# LED_STRING_MANAGER_REV_1.net
KiCad netlist of a schematic drawn in EAGLE
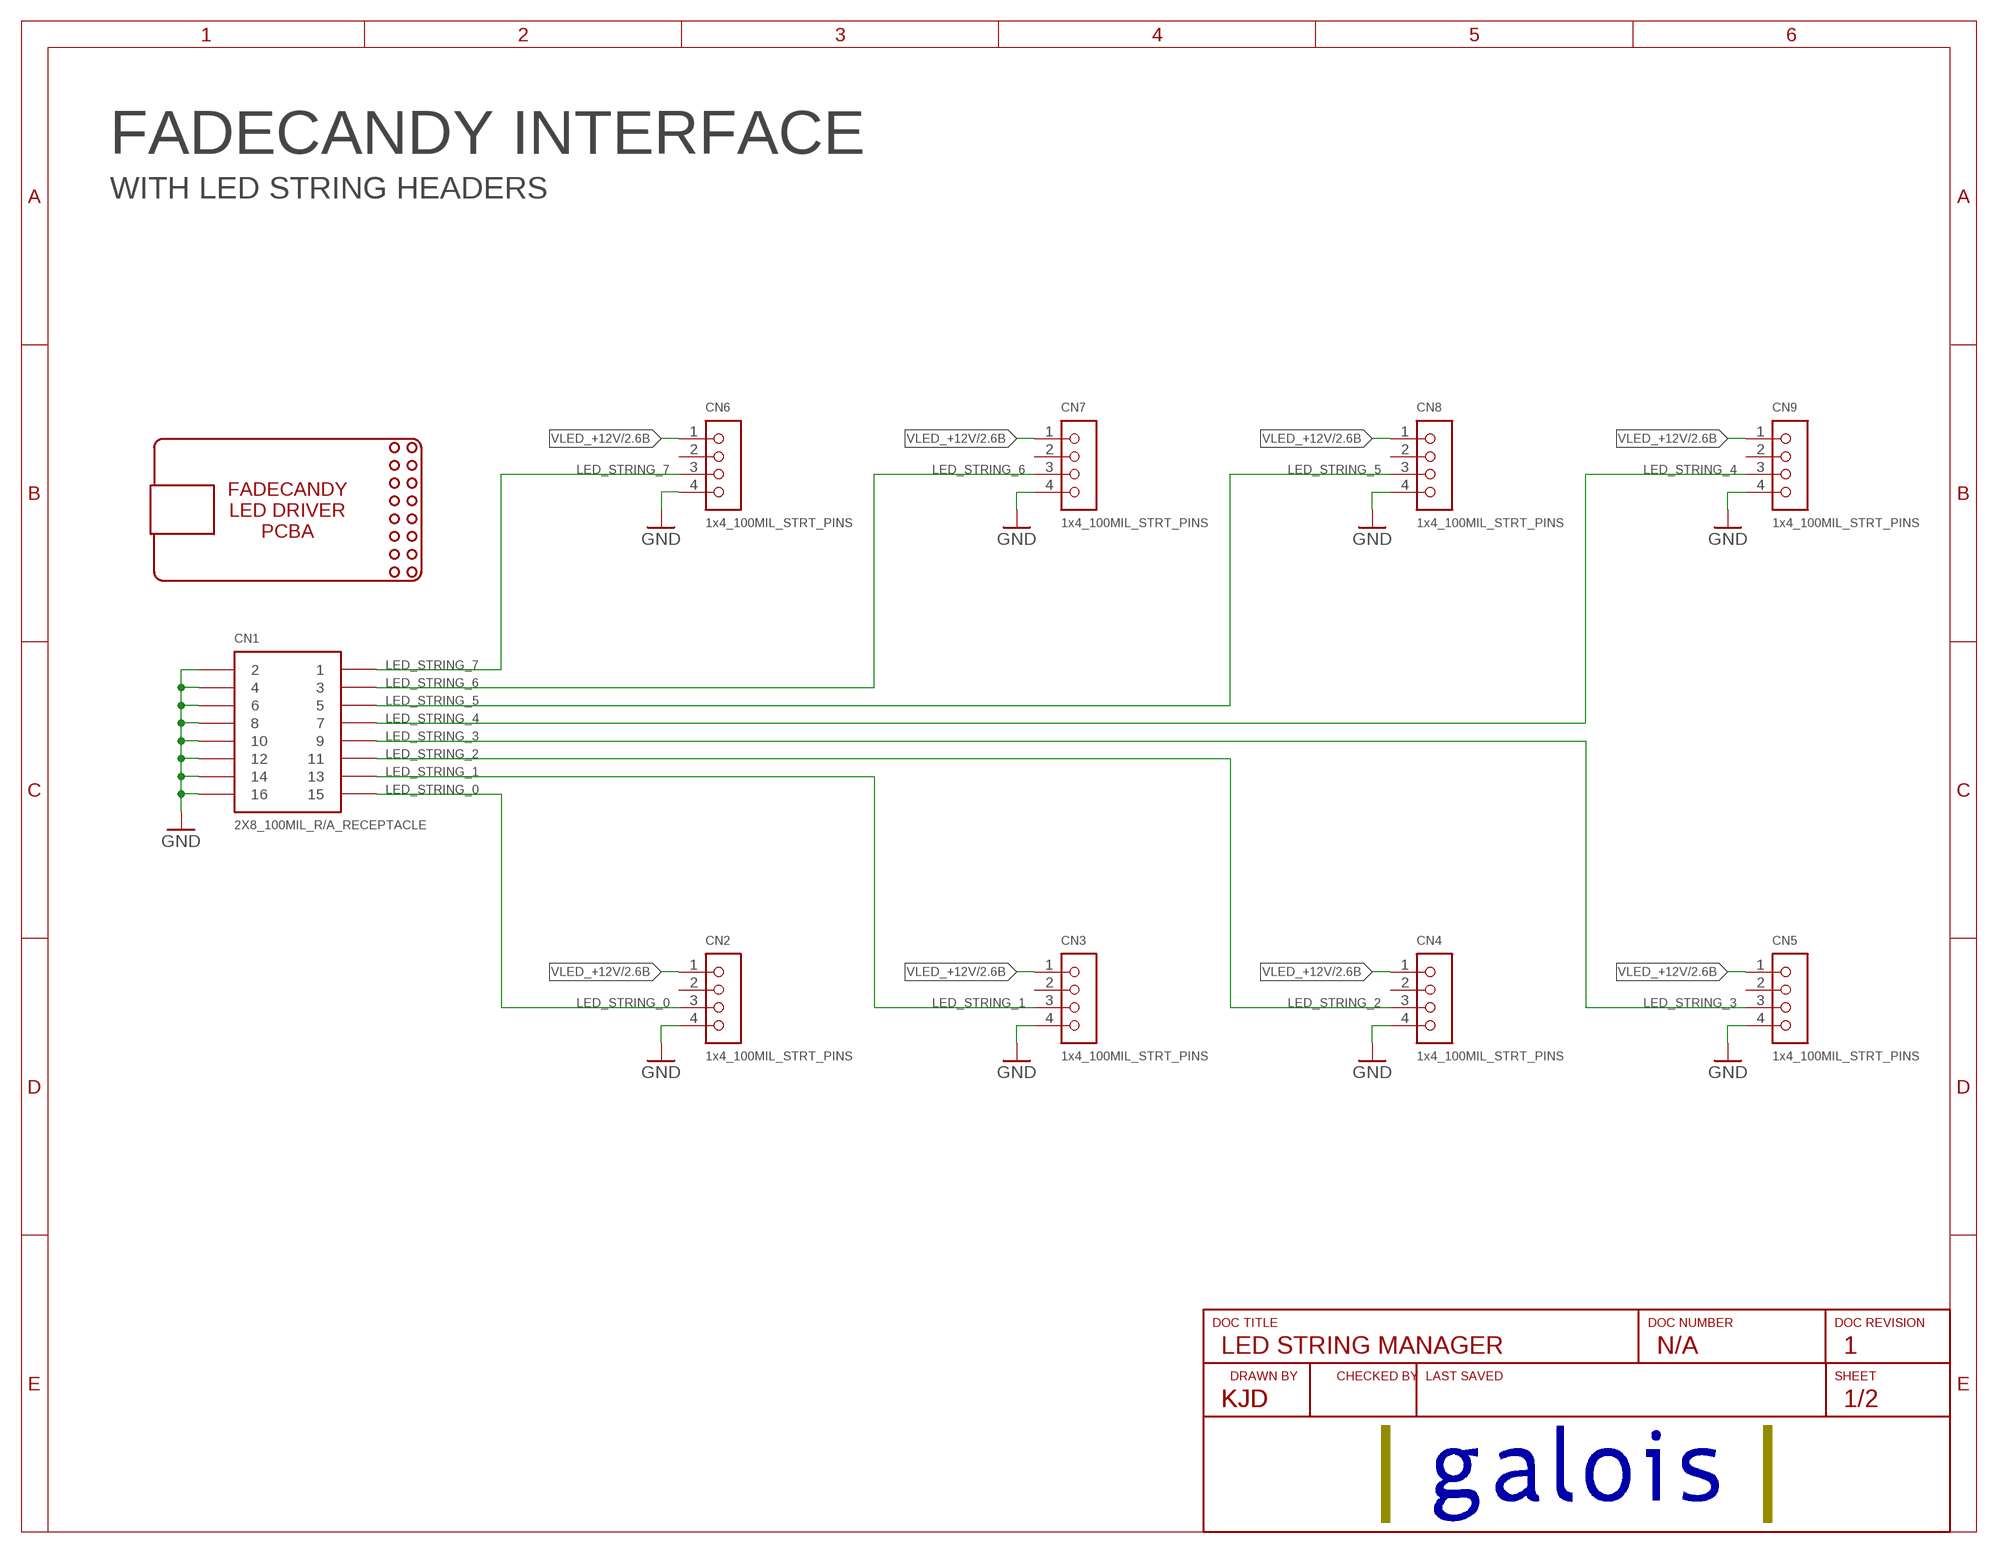
[diagram p0: schematic, sheet 1]
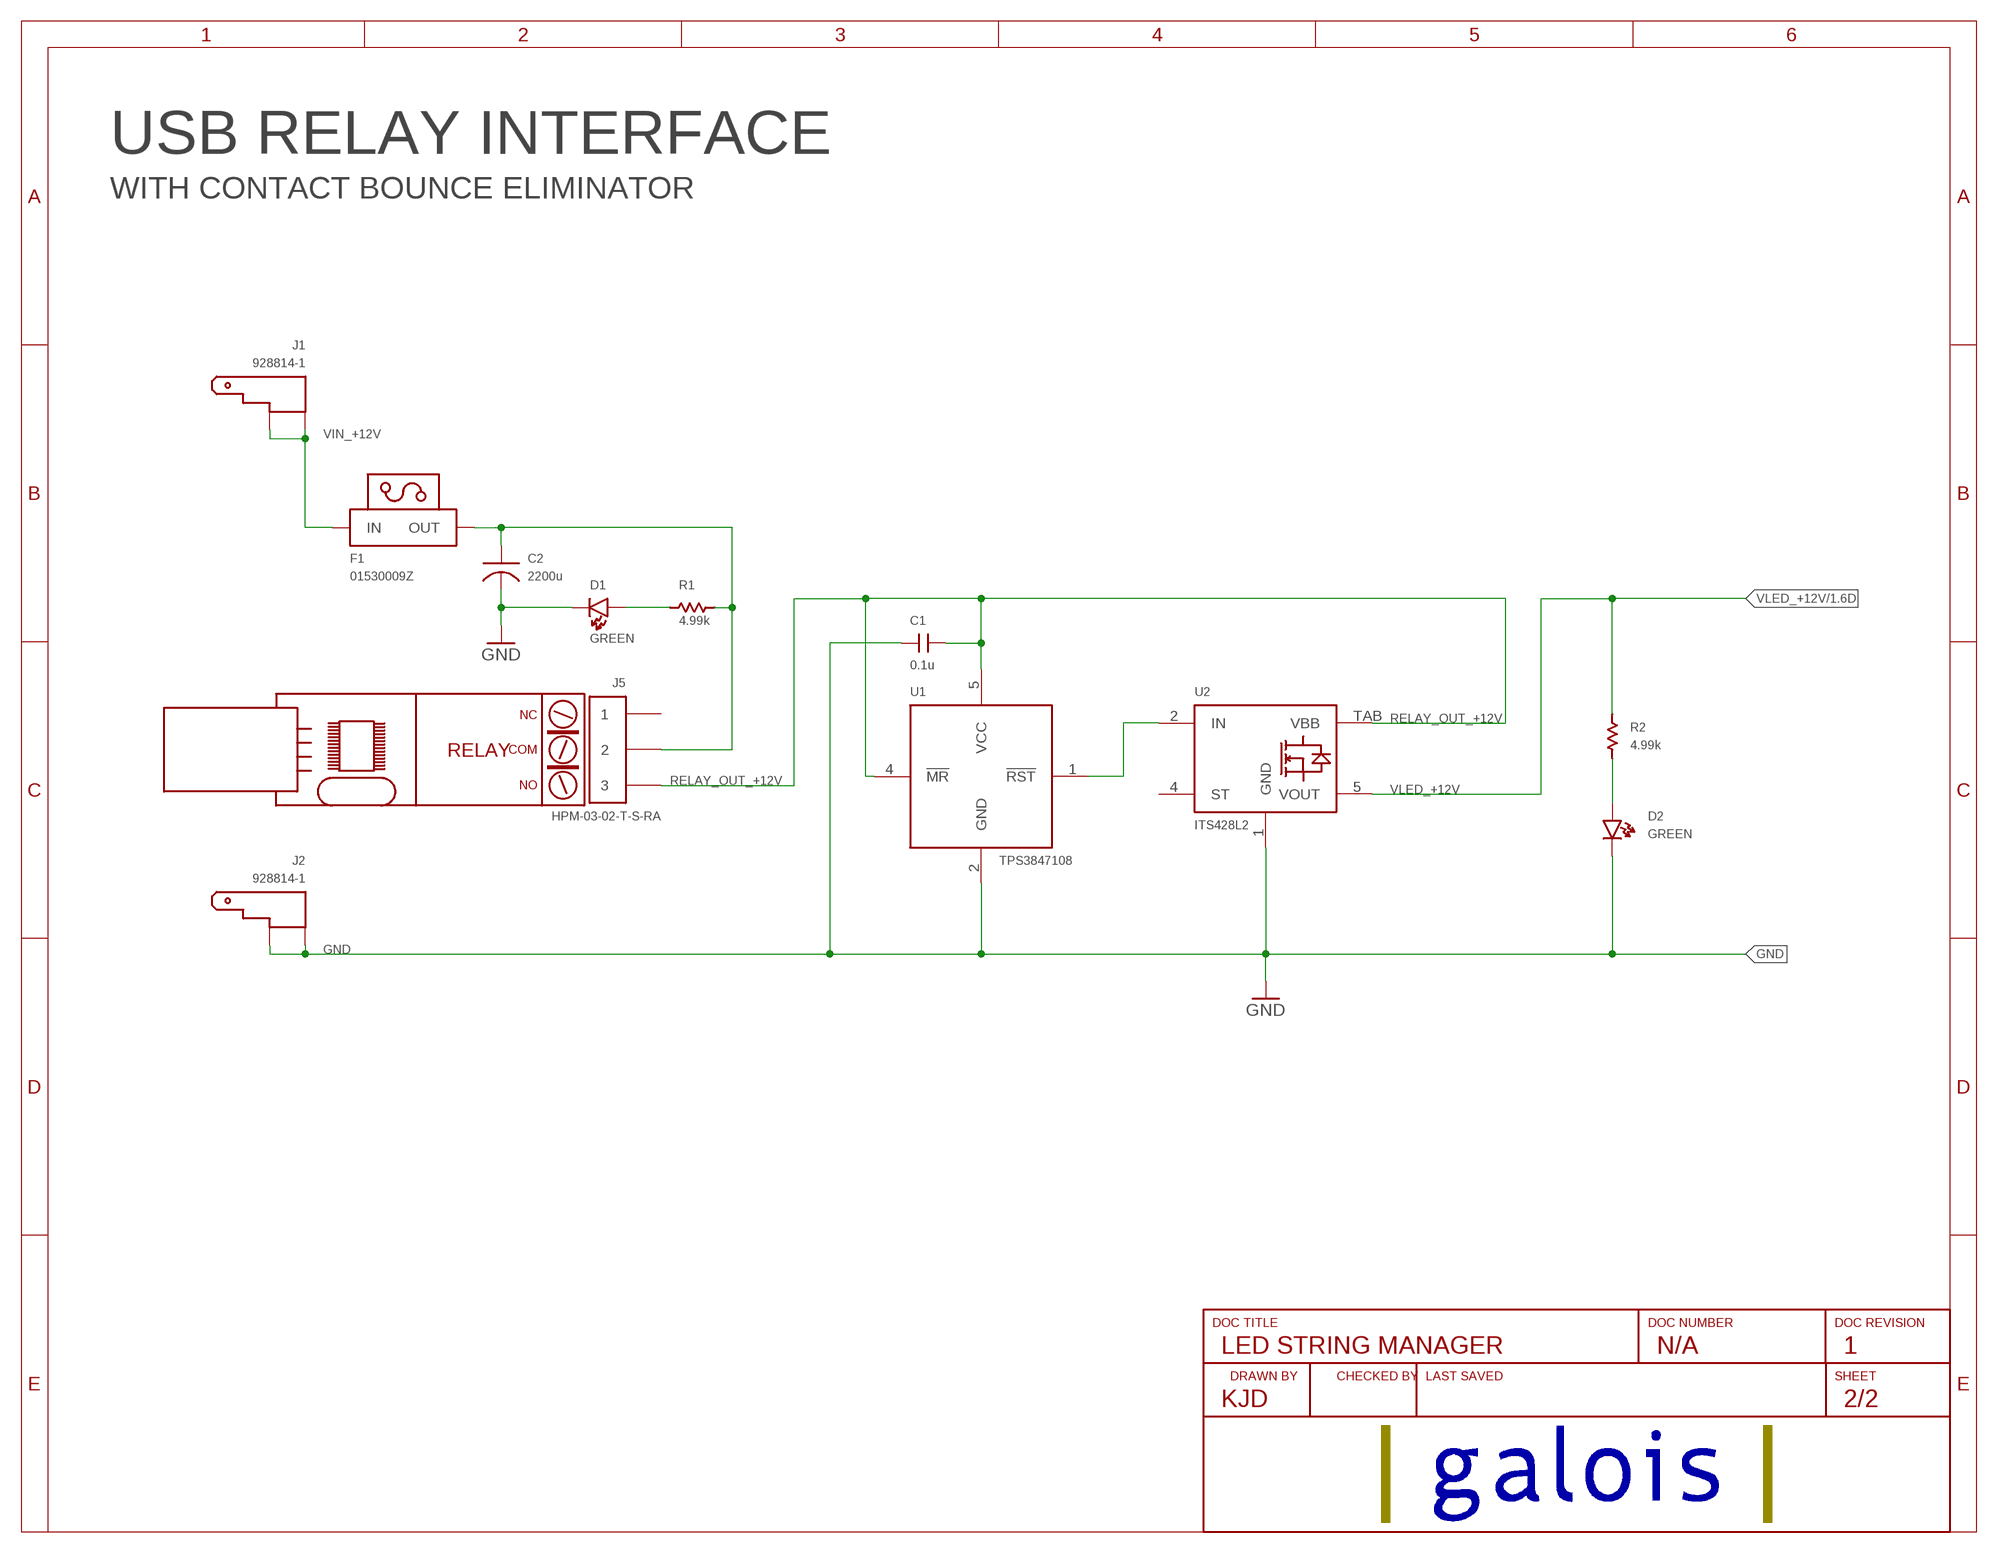
[diagram p1: schematic, sheet 2]

(export (version "E")
  (design (tool "Eeschema 10.0.6"))
  (components
    (comp (ref "CN1")
      (value "2X8_100MIL_R/A_RECEPTACLE")
      (footprint "eagle-import:2X8_100MIL_R_A")
      (fields (field (name "MPN") "PPPC082LJBN-RC"))
      (libsource (lib "eagle-import") (part "2X8_RIGHT_ANGLE"))
    )
    (comp (ref "CN2")
      (value "1x4_100MIL_STRT_PINS")
      (footprint "eagle-import:1X4_0901361204")
      (fields (field (name "MPN") "0901361204"))
      (libsource (lib "eagle-import") (part "MOLEX_CGRID_III_0901361204"))
    )
    (comp (ref "CN3")
      (value "1x4_100MIL_STRT_PINS")
      (footprint "eagle-import:1X4_0901361204")
      (fields (field (name "MPN") "0901361204"))
      (libsource (lib "eagle-import") (part "MOLEX_CGRID_III_0901361204"))
    )
    (comp (ref "CN4")
      (value "1x4_100MIL_STRT_PINS")
      (footprint "eagle-import:1X4_0901361204")
      (fields (field (name "MPN") "0901361204"))
      (libsource (lib "eagle-import") (part "MOLEX_CGRID_III_0901361204"))
    )
    (comp (ref "CN5")
      (value "1x4_100MIL_STRT_PINS")
      (footprint "eagle-import:1X4_0901361204")
      (fields (field (name "MPN") "0901361204"))
      (libsource (lib "eagle-import") (part "MOLEX_CGRID_III_0901361204"))
    )
    (comp (ref "CN6")
      (value "1x4_100MIL_STRT_PINS")
      (footprint "eagle-import:1X4_0901361204")
      (fields (field (name "MPN") "0901361204"))
      (libsource (lib "eagle-import") (part "MOLEX_CGRID_III_0901361204"))
    )
    (comp (ref "CN7")
      (value "1x4_100MIL_STRT_PINS")
      (footprint "eagle-import:1X4_0901361204")
      (fields (field (name "MPN") "0901361204"))
      (libsource (lib "eagle-import") (part "MOLEX_CGRID_III_0901361204"))
    )
    (comp (ref "CN8")
      (value "1x4_100MIL_STRT_PINS")
      (footprint "eagle-import:1X4_0901361204")
      (fields (field (name "MPN") "0901361204"))
      (libsource (lib "eagle-import") (part "MOLEX_CGRID_III_0901361204"))
    )
    (comp (ref "CN9")
      (value "1x4_100MIL_STRT_PINS")
      (footprint "eagle-import:1X4_0901361204")
      (fields (field (name "MPN") "0901361204"))
      (libsource (lib "eagle-import") (part "MOLEX_CGRID_III_0901361204"))
    )
    (comp (ref "U$3")
      (value "FADECANDY_PCB_FOOTPRINT")
      (footprint "eagle-import:FADECANDY_PCB_FOOTPRINT")
      (libsource (lib "eagle-import") (part "FADECANDY_PCB_FOOTPRINT"))
    )
    (comp (ref "C1")
      (value "0.1u")
      (footprint "eagle-import:EIA0603")
      (fields (field (name "MPN") "CL10B104KB8NNNC"))
      (libsource (lib "eagle-import") (part "C_SMDC0603"))
    )
    (comp (ref "C2")
      (value "2200u")
      (footprint "eagle-import:PANASONIC_HD_12.5MM")
      (fields (field (name "MPN") "EEU-HD1E222"))
      (libsource (lib "eagle-import") (part "C_POLARIZED_DIA_12.5MM_LEADS_5MM"))
    )
    (comp (ref "D1")
      (value "GREEN")
      (footprint "eagle-import:EIA0603_LED")
      (fields (field (name "MPN") "LG Q396-PS-35"))
      (libsource (lib "eagle-import") (part "LED_SMD"))
    )
    (comp (ref "D2")
      (value "GREEN")
      (footprint "eagle-import:EIA0603_LED")
      (fields (field (name "MPN") "LG Q396-PS-35"))
      (libsource (lib "eagle-import") (part "LED_SMD"))
    )
    (comp (ref "F1")
      (value "01530009Z")
      (footprint "eagle-import:LITTELFUSE_MINI_BLADE_HOLDER_01530009")
      (fields (field (name "MPN") "01530009Z"))
      (libsource (lib "eagle-import") (part "FUSE_HOLDER_AUTOMOTIVE_MINI_BLADE"))
    )
    (comp (ref "J1")
      (value "928814-1")
      (footprint "eagle-import:FASTON_MALE_SERIES_250_THRU_R_A")
      (fields (field (name "MPN") "928814-1"))
      (libsource (lib "eagle-import") (part "FASTON_PCB_THRU_R/A"))
    )
    (comp (ref "J2")
      (value "928814-1")
      (footprint "eagle-import:FASTON_MALE_SERIES_250_THRU_R_A")
      (fields (field (name "MPN") "928814-1"))
      (libsource (lib "eagle-import") (part "FASTON_PCB_THRU_R/A"))
    )
    (comp (ref "J5")
      (value "HPM-03-02-T-S-RA")
      (footprint "eagle-import:HPM_1X3_R_A")
      (fields (field (name "MPN") "HPM-03-02-T-S-RA"))
      (libsource (lib "eagle-import") (part "HPM_1X3_R/A"))
    )
    (comp (ref "R1")
      (value "4.99k")
      (footprint "eagle-import:EIA0603")
      (fields (field (name "MPN") "ERJ-3EKF4991V"))
      (libsource (lib "eagle-import") (part "R_SMDR0603"))
    )
    (comp (ref "R2")
      (value "4.99k")
      (footprint "eagle-import:EIA0603")
      (fields (field (name "MPN") "ERJ-3EKF4991V"))
      (libsource (lib "eagle-import") (part "R_SMDR0603"))
    )
    (comp (ref "U$4")
      (value "USB_RELAY_PCB_FOOTPRINT")
      (footprint "eagle-import:USB_RELAY_PCB_FOOTPRINT")
      (libsource (lib "eagle-import") (part "USB_RELAY_PCB_FOOTPRINT"))
    )
    (comp (ref "U1")
      (value "TPS3847108")
      (footprint "eagle-import:SOT23-5")
      (fields (field (name "MPN") "TPS3847108DBVR"))
      (libsource (lib "eagle-import") (part "TPS3847"))
    )
    (comp (ref "U2")
      (value "ITS428L2")
      (footprint "eagle-import:PG-TO252-5-11")
      (fields (field (name "MPN") "ITS428L2ATMA1"))
      (libsource (lib "eagle-import") (part "ITS428L2"))
    )
  )
  (nets
    (net (code "1") (name "GND") (class "Default")
      (node (ref "C1") (pin "P$1") (pinfunction "P$1_P$1") (pintype "passive"))
      (node (ref "C2") (pin "C-") (pinfunction "C-_C-") (pintype "bidirectional"))
      (node (ref "CN1") (pin "10") (pinfunction "10_10") (pintype "bidirectional"))
      (node (ref "CN1") (pin "12") (pinfunction "12_12") (pintype "bidirectional"))
      (node (ref "CN1") (pin "14") (pinfunction "14_14") (pintype "bidirectional"))
      (node (ref "CN1") (pin "16") (pinfunction "16_16") (pintype "bidirectional"))
      (node (ref "CN1") (pin "2") (pinfunction "2_2") (pintype "bidirectional"))
      (node (ref "CN1") (pin "4") (pinfunction "4_4") (pintype "bidirectional"))
      (node (ref "CN1") (pin "6") (pinfunction "6_6") (pintype "bidirectional"))
      (node (ref "CN1") (pin "8") (pinfunction "8_8") (pintype "bidirectional"))
      (node (ref "CN2") (pin "4") (pinfunction "4_4") (pintype "bidirectional"))
      (node (ref "CN3") (pin "4") (pinfunction "4_4") (pintype "bidirectional"))
      (node (ref "CN4") (pin "4") (pinfunction "4_4") (pintype "bidirectional"))
      (node (ref "CN5") (pin "4") (pinfunction "4_4") (pintype "bidirectional"))
      (node (ref "CN6") (pin "4") (pinfunction "4_4") (pintype "bidirectional"))
      (node (ref "CN7") (pin "4") (pinfunction "4_4") (pintype "bidirectional"))
      (node (ref "CN8") (pin "4") (pinfunction "4_4") (pintype "bidirectional"))
      (node (ref "CN9") (pin "4") (pinfunction "4_4") (pintype "bidirectional"))
      (node (ref "D1") (pin "C") (pinfunction "C_C") (pintype "passive"))
      (node (ref "D2") (pin "C") (pinfunction "C_C") (pintype "passive"))
      (node (ref "J2") (pin "1") (pinfunction "1_1") (pintype "bidirectional"))
      (node (ref "J2") (pin "2") (pinfunction "2_2") (pintype "bidirectional"))
      (node (ref "U1") (pin "2") (pinfunction "GND_2") (pintype "bidirectional"))
      (node (ref "U2") (pin "1") (pinfunction "GND_1") (pintype "bidirectional"))
    )
    (net (code "2") (name "LED_STRING_0") (class "Default")
      (node (ref "CN1") (pin "15") (pinfunction "15_15") (pintype "bidirectional"))
      (node (ref "CN2") (pin "3") (pinfunction "3_3") (pintype "bidirectional"))
    )
    (net (code "3") (name "LED_STRING_1") (class "Default")
      (node (ref "CN1") (pin "13") (pinfunction "13_13") (pintype "bidirectional"))
      (node (ref "CN3") (pin "3") (pinfunction "3_3") (pintype "bidirectional"))
    )
    (net (code "4") (name "LED_STRING_2") (class "Default")
      (node (ref "CN1") (pin "11") (pinfunction "11_11") (pintype "bidirectional"))
      (node (ref "CN4") (pin "3") (pinfunction "3_3") (pintype "bidirectional"))
    )
    (net (code "5") (name "LED_STRING_3") (class "Default")
      (node (ref "CN1") (pin "9") (pinfunction "9_9") (pintype "bidirectional"))
      (node (ref "CN5") (pin "3") (pinfunction "3_3") (pintype "bidirectional"))
    )
    (net (code "6") (name "LED_STRING_4") (class "Default")
      (node (ref "CN1") (pin "7") (pinfunction "7_7") (pintype "bidirectional"))
      (node (ref "CN9") (pin "3") (pinfunction "3_3") (pintype "bidirectional"))
    )
    (net (code "7") (name "LED_STRING_5") (class "Default")
      (node (ref "CN1") (pin "5") (pinfunction "5_5") (pintype "bidirectional"))
      (node (ref "CN8") (pin "3") (pinfunction "3_3") (pintype "bidirectional"))
    )
    (net (code "8") (name "LED_STRING_6") (class "Default")
      (node (ref "CN1") (pin "3") (pinfunction "3_3") (pintype "bidirectional"))
      (node (ref "CN7") (pin "3") (pinfunction "3_3") (pintype "bidirectional"))
    )
    (net (code "9") (name "LED_STRING_7") (class "Default")
      (node (ref "CN1") (pin "1") (pinfunction "1_1") (pintype "bidirectional"))
      (node (ref "CN6") (pin "3") (pinfunction "3_3") (pintype "bidirectional"))
    )
    (net (code "10") (name "Net-(D1-PadA)") (class "Default")
      (node (ref "D1") (pin "A") (pinfunction "A_A") (pintype "passive"))
      (node (ref "R1") (pin "P$1") (pinfunction "P$1_P$1") (pintype "passive"))
    )
    (net (code "11") (name "Net-(D2-PadA)") (class "Default")
      (node (ref "D2") (pin "A") (pinfunction "A_A") (pintype "passive"))
      (node (ref "R2") (pin "P$1") (pinfunction "P$1_P$1") (pintype "passive"))
    )
    (net (code "12") (name "Net-(F1-OUT)") (class "Default")
      (node (ref "C2") (pin "C+") (pinfunction "C+_C+") (pintype "bidirectional"))
      (node (ref "F1") (pin "2") (pinfunction "OUT_2") (pintype "bidirectional"))
      (node (ref "J5") (pin "2") (pinfunction "2_2") (pintype "bidirectional"))
      (node (ref "R1") (pin "P$2") (pinfunction "P$2_P$2") (pintype "passive"))
    )
    (net (code "13") (name "Net-(U1-~{RST})") (class "Default")
      (node (ref "U1") (pin "1") (pinfunction "~{RST}_1") (pintype "bidirectional"))
      (node (ref "U2") (pin "2") (pinfunction "IN_2") (pintype "bidirectional"))
    )
    (net (code "14") (name "RELAY_OUT_+12V") (class "Default")
      (node (ref "C1") (pin "P$2") (pinfunction "P$2_P$2") (pintype "passive"))
      (node (ref "J5") (pin "3") (pinfunction "3_3") (pintype "bidirectional"))
      (node (ref "U1") (pin "4") (pinfunction "~{MR}_4") (pintype "bidirectional"))
      (node (ref "U1") (pin "5") (pinfunction "VCC_5") (pintype "bidirectional"))
      (node (ref "U2") (pin "TAB") (pinfunction "VBB_TAB") (pintype "bidirectional"))
    )
    (net (code "15") (name "VIN_+12V") (class "Default")
      (node (ref "F1") (pin "1") (pinfunction "IN_1") (pintype "bidirectional"))
      (node (ref "J1") (pin "1") (pinfunction "1_1") (pintype "bidirectional"))
      (node (ref "J1") (pin "2") (pinfunction "2_2") (pintype "bidirectional"))
    )
    (net (code "16") (name "VLED_+12V") (class "Default")
      (node (ref "CN2") (pin "1") (pinfunction "1_1") (pintype "bidirectional"))
      (node (ref "CN3") (pin "1") (pinfunction "1_1") (pintype "bidirectional"))
      (node (ref "CN4") (pin "1") (pinfunction "1_1") (pintype "bidirectional"))
      (node (ref "CN5") (pin "1") (pinfunction "1_1") (pintype "bidirectional"))
      (node (ref "CN6") (pin "1") (pinfunction "1_1") (pintype "bidirectional"))
      (node (ref "CN7") (pin "1") (pinfunction "1_1") (pintype "bidirectional"))
      (node (ref "CN8") (pin "1") (pinfunction "1_1") (pintype "bidirectional"))
      (node (ref "CN9") (pin "1") (pinfunction "1_1") (pintype "bidirectional"))
      (node (ref "R2") (pin "P$2") (pinfunction "P$2_P$2") (pintype "passive"))
      (node (ref "U2") (pin "5") (pinfunction "VOUT_5") (pintype "bidirectional"))
    )
    (net (code "17") (name "unconnected-(CN2-Pad2)") (class "Default")
      (node (ref "CN2") (pin "2") (pinfunction "2_2") (pintype "bidirectional"))
    )
    (net (code "18") (name "unconnected-(CN3-Pad2)") (class "Default")
      (node (ref "CN3") (pin "2") (pinfunction "2_2") (pintype "bidirectional"))
    )
    (net (code "19") (name "unconnected-(CN4-Pad2)") (class "Default")
      (node (ref "CN4") (pin "2") (pinfunction "2_2") (pintype "bidirectional"))
    )
    (net (code "20") (name "unconnected-(CN5-Pad2)") (class "Default")
      (node (ref "CN5") (pin "2") (pinfunction "2_2") (pintype "bidirectional"))
    )
    (net (code "21") (name "unconnected-(CN6-Pad2)") (class "Default")
      (node (ref "CN6") (pin "2") (pinfunction "2_2") (pintype "bidirectional"))
    )
    (net (code "22") (name "unconnected-(CN7-Pad2)") (class "Default")
      (node (ref "CN7") (pin "2") (pinfunction "2_2") (pintype "bidirectional"))
    )
    (net (code "23") (name "unconnected-(CN8-Pad2)") (class "Default")
      (node (ref "CN8") (pin "2") (pinfunction "2_2") (pintype "bidirectional"))
    )
    (net (code "24") (name "unconnected-(CN9-Pad2)") (class "Default")
      (node (ref "CN9") (pin "2") (pinfunction "2_2") (pintype "bidirectional"))
    )
    (net (code "25") (name "unconnected-(J5-Pad1)") (class "Default")
      (node (ref "J5") (pin "1") (pinfunction "1_1") (pintype "bidirectional"))
    )
    (net (code "26") (name "unconnected-(U2-ST-Pad4)") (class "Default")
      (node (ref "U2") (pin "4") (pinfunction "ST_4") (pintype "bidirectional"))
    )
  )
)
